# C1G14-BreakoutSMT.net
KiCad netlist of a schematic drawn in EAGLE
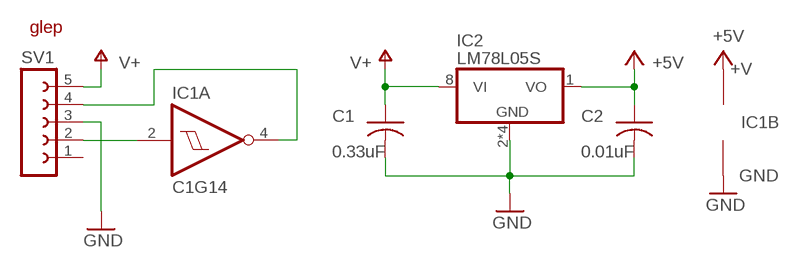
[diagram p0: schematic, sheet 1]

(export (version "E")
  (design (tool "Eeschema 10.0.6"))
  (components
    (comp (ref "C1")
      (value "0.33uF")
      (footprint "eagle-import:C0805")
      (libsource (lib "eagle-import") (part "C-USC0805"))
    )
    (comp (ref "C2")
      (value "0.01uF")
      (footprint "eagle-import:C0805")
      (libsource (lib "eagle-import") (part "C-USC0805"))
    )
    (comp (ref "IC1")
      (value "C1G14")
      (footprint "eagle-import:SOT-25")
      (libsource (lib "eagle-import") (part "C1G14"))
    )
    (comp (ref "IC2")
      (value "LM78L05S")
      (footprint "eagle-import:SO08")
      (libsource (lib "eagle-import") (part "LM78L05S"))
    )
    (comp (ref "SV1")
      (value "FE05-1")
      (footprint "eagle-import:FE05-1")
      (libsource (lib "eagle-import") (part "FE05-1"))
    )
    (comp (ref "U$1")
      (value "GLEP")
      (footprint "eagle-import:GLEP")
      (libsource (lib "eagle-import") (part "GLEP"))
    )
  )
  (nets
    (net (code "1") (name "+5V") (class "Default")
      (node (ref "C2") (pin "1") (pinfunction "1_1") (pintype "passive"))
      (node (ref "IC1") (pin "5") (pinfunction "V+_5") (pintype "power_in"))
      (node (ref "IC2") (pin "1") (pinfunction "VO_1") (pintype "passive"))
    )
    (net (code "2") (name "GND") (class "Default")
      (node (ref "C1") (pin "2") (pinfunction "2_2") (pintype "passive"))
      (node (ref "C2") (pin "2") (pinfunction "2_2") (pintype "passive"))
      (node (ref "IC1") (pin "3") (pinfunction "GND_3") (pintype "passive"))
      (node (ref "IC2") (pin "2") (pinfunction "GND_2") (pintype "passive"))
      (node (ref "IC2") (pin "3") (pinfunction "GND_3") (pintype "passive"))
      (node (ref "IC2") (pin "6") (pinfunction "GND_6") (pintype "passive"))
      (node (ref "IC2") (pin "7") (pinfunction "GND_7") (pintype "passive"))
      (node (ref "SV1") (pin "3") (pinfunction "3_3") (pintype "passive"))
    )
    (net (code "3") (name "Net-(IC1A-A)") (class "Default")
      (node (ref "IC1") (pin "2") (pinfunction "A_2") (pintype "input"))
      (node (ref "SV1") (pin "2") (pinfunction "2_2") (pintype "passive"))
    )
    (net (code "4") (name "Net-(IC1A-Y)") (class "Default")
      (node (ref "IC1") (pin "4") (pinfunction "Y_4") (pintype "output"))
      (node (ref "SV1") (pin "4") (pinfunction "4_4") (pintype "passive"))
    )
    (net (code "5") (name "V+") (class "Default")
      (node (ref "C1") (pin "1") (pinfunction "1_1") (pintype "passive"))
      (node (ref "IC2") (pin "8") (pinfunction "VI_8") (pintype "input"))
      (node (ref "SV1") (pin "5") (pinfunction "5_5") (pintype "passive"))
    )
    (net (code "6") (name "unconnected-(SV1-Pad1)") (class "Default")
      (node (ref "SV1") (pin "1") (pinfunction "1_1") (pintype "passive"))
    )
  )
)
